# diytextool.net
KiCad netlist of a schematic drawn in EAGLE
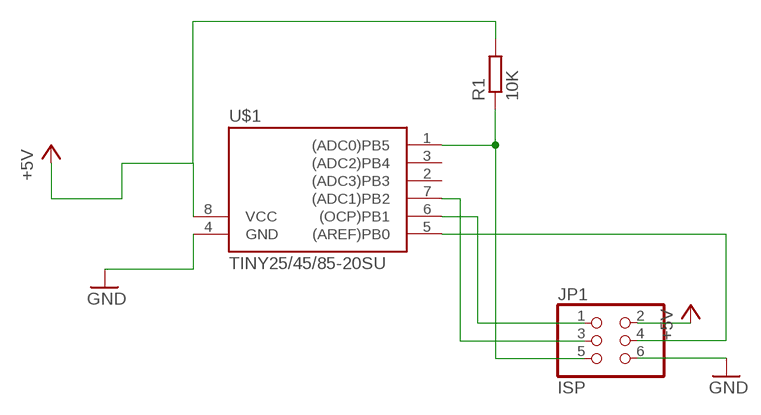
[diagram p0: schematic, sheet 1]

(export (version "E")
  (design (tool "Eeschema 10.0.6"))
  (components
    (comp (ref "JP1")
      (value "ISP")
      (footprint "eagle-import:2X03SMD")
      (libsource (lib "eagle-import") (part "PINHD-2X03_2.54-SMD"))
    )
    (comp (ref "R1")
      (value "10K")
      (footprint "eagle-import:R0603")
      (libsource (lib "eagle-import") (part "R-EU_R0603"))
    )
    (comp (ref "U$1")
      (value "TINY25/45/85-20SU")
      (footprint "eagle-import:SOIC8")
      (libsource (lib "eagle-import") (part "TINY25/45/85-20SU"))
    )
  )
  (nets
    (net (code "1") (name "+5V") (class "Default")
      (node (ref "JP1") (pin "2") (pinfunction "2_2") (pintype "passive"))
      (node (ref "R1") (pin "2") (pinfunction "2_2") (pintype "passive"))
      (node (ref "U$1") (pin "8") (pinfunction "VCC_8") (pintype "power_in"))
    )
    (net (code "2") (name "GND") (class "Default")
      (node (ref "JP1") (pin "6") (pinfunction "6_6") (pintype "passive"))
      (node (ref "U$1") (pin "4") (pinfunction "GND_4") (pintype "power_in"))
    )
    (net (code "3") (name "Net-(U$1-(ADC0)PB5)") (class "Default")
      (node (ref "JP1") (pin "5") (pinfunction "5_5") (pintype "passive"))
      (node (ref "R1") (pin "1") (pinfunction "1_1") (pintype "passive"))
      (node (ref "U$1") (pin "1") (pinfunction "(ADC0)PB5_1") (pintype "bidirectional"))
    )
    (net (code "4") (name "Net-(U$1-(ADC1)PB2)") (class "Default")
      (node (ref "JP1") (pin "3") (pinfunction "3_3") (pintype "passive"))
      (node (ref "U$1") (pin "7") (pinfunction "(ADC1)PB2_7") (pintype "bidirectional"))
    )
    (net (code "5") (name "Net-(U$1-(AREF)PB0)") (class "Default")
      (node (ref "JP1") (pin "4") (pinfunction "4_4") (pintype "passive"))
      (node (ref "U$1") (pin "5") (pinfunction "(AREF)PB0_5") (pintype "bidirectional"))
    )
    (net (code "6") (name "Net-(U$1-(OCP)PB1)") (class "Default")
      (node (ref "JP1") (pin "1") (pinfunction "1_1") (pintype "passive"))
      (node (ref "U$1") (pin "6") (pinfunction "(OCP)PB1_6") (pintype "bidirectional"))
    )
    (net (code "7") (name "unconnected-(U$1-(ADC2)PB4-Pad3)") (class "Default")
      (node (ref "U$1") (pin "3") (pinfunction "(ADC2)PB4_3") (pintype "bidirectional"))
    )
    (net (code "8") (name "unconnected-(U$1-(ADC3)PB3-Pad2)") (class "Default")
      (node (ref "U$1") (pin "2") (pinfunction "(ADC3)PB3_2") (pintype "bidirectional"))
    )
  )
)
